# USB_Converter.net
KiCad netlist of a schematic drawn in Altium Designer
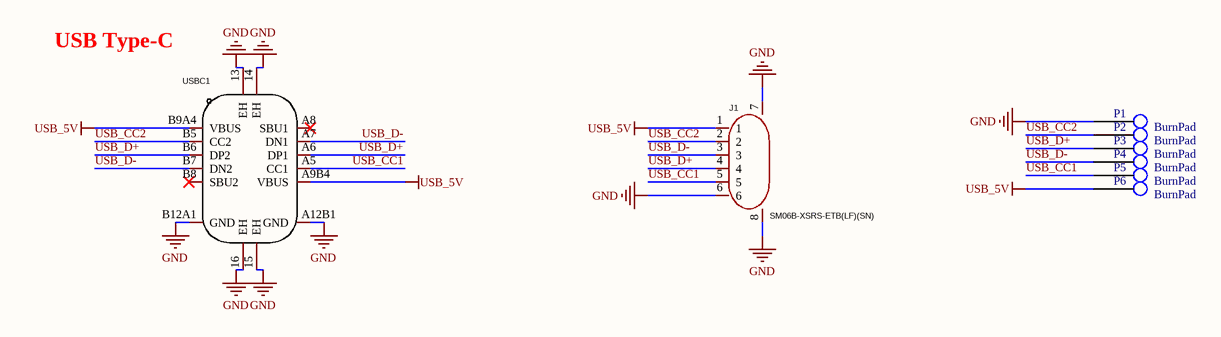
[diagram p0: USB_Converter.SchDoc]

(export (version "E")
  (design (tool "Eeschema 10.0.6"))
  (components
    (comp (ref "J1")
      (value "SM06B-XSRS-ETB(LF)(SN)")
      (footprint "CONN-SMD_6P-P0.6")
      (fields (field (name "MANUFACTURER") "JST"))
      (libsource (lib "XSR0.6") (part "SM06B-XSRS-ETB(LF)(SN)"))
    )
    (comp (ref "P1") (value "BurnPad") (footprint "BurnPad_0.5mm") (libsource (lib "Pad") (part "BurnPad")))
    (comp (ref "P2") (value "BurnPad") (footprint "BurnPad_0.5mm") (libsource (lib "Pad") (part "BurnPad")))
    (comp (ref "P3") (value "BurnPad") (footprint "BurnPad_0.5mm") (libsource (lib "Pad") (part "BurnPad")))
    (comp (ref "P4") (value "BurnPad") (footprint "BurnPad_0.5mm") (libsource (lib "Pad") (part "BurnPad")))
    (comp (ref "P5") (value "BurnPad") (footprint "BurnPad_0.5mm") (libsource (lib "Pad") (part "BurnPad")))
    (comp (ref "P6") (value "BurnPad") (footprint "BurnPad_0.5mm") (libsource (lib "Pad") (part "BurnPad")))
    (comp (ref "USBC1")
      (value "918-418K2024S40000")
      (footprint "USB-C-SMD_TYPE-C-USB-4")
      (fields (field (name "MANUFACTURER") "精拓金"))
      (libsource (lib "TYPE-C") (part "918-418K2024S40000"))
    )
  )
  (nets
    (net (code "1") (name "/USB_CC1") (class "Default")
      (node (ref "J1") (pin "5") (pinfunction "5_5") (pintype "passive"))
      (node (ref "P5") (pin "1") (pinfunction "1_1") (pintype "passive"))
      (node (ref "USBC1") (pin "A5") (pinfunction "CC1_A5") (pintype "passive"))
    )
    (net (code "2") (name "/USB_CC2") (class "Default")
      (node (ref "J1") (pin "2") (pinfunction "2_2") (pintype "passive"))
      (node (ref "P2") (pin "1") (pinfunction "1_1") (pintype "passive"))
      (node (ref "USBC1") (pin "B5") (pinfunction "CC2_B5") (pintype "passive"))
    )
    (net (code "3") (name "/USB_D+") (class "Default")
      (node (ref "J1") (pin "4") (pinfunction "4_4") (pintype "passive"))
      (node (ref "P3") (pin "1") (pinfunction "1_1") (pintype "passive"))
      (node (ref "USBC1") (pin "A6") (pinfunction "DP1_A6") (pintype "passive"))
      (node (ref "USBC1") (pin "B6") (pinfunction "DP2_B6") (pintype "passive"))
    )
    (net (code "4") (name "/USB_D-") (class "Default")
      (node (ref "J1") (pin "3") (pinfunction "3_3") (pintype "passive"))
      (node (ref "P4") (pin "1") (pinfunction "1_1") (pintype "passive"))
      (node (ref "USBC1") (pin "A7") (pinfunction "DN1_A7") (pintype "passive"))
      (node (ref "USBC1") (pin "B7") (pinfunction "DN2_B7") (pintype "passive"))
    )
    (net (code "5") (name "GND") (class "Default")
      (node (ref "J1") (pin "6") (pinfunction "6_6") (pintype "passive"))
      (node (ref "J1") (pin "7") (pinfunction "7_7") (pintype "passive"))
      (node (ref "J1") (pin "8") (pinfunction "8_8") (pintype "passive"))
      (node (ref "P1") (pin "1") (pinfunction "1_1") (pintype "passive"))
      (node (ref "USBC1") (pin "13") (pinfunction "EH_13") (pintype "passive"))
      (node (ref "USBC1") (pin "14") (pinfunction "EH_14") (pintype "passive"))
      (node (ref "USBC1") (pin "15") (pinfunction "EH_15") (pintype "passive"))
      (node (ref "USBC1") (pin "16") (pinfunction "EH_16") (pintype "passive"))
      (node (ref "USBC1") (pin "A12B1") (pinfunction "GND_A12B1") (pintype "passive"))
      (node (ref "USBC1") (pin "B12A1") (pinfunction "GND_B12A1") (pintype "passive"))
    )
    (net (code "6") (name "USB_5V") (class "Default")
      (node (ref "J1") (pin "1") (pinfunction "1_1") (pintype "passive"))
      (node (ref "P6") (pin "1") (pinfunction "1_1") (pintype "passive"))
      (node (ref "USBC1") (pin "A9B4") (pinfunction "VBUS_A9B4") (pintype "passive"))
      (node (ref "USBC1") (pin "B9A4") (pinfunction "VBUS_B9A4") (pintype "passive"))
    )
    (net (code "7") (name "unconnected-(USBC1-SBU1-PadA8)") (class "Default")
      (node (ref "USBC1") (pin "A8") (pinfunction "SBU1_A8") (pintype "passive+no_connect"))
    )
    (net (code "8") (name "unconnected-(USBC1-SBU2-PadB8)") (class "Default")
      (node (ref "USBC1") (pin "B8") (pinfunction "SBU2_B8") (pintype "passive+no_connect"))
    )
  )
)
